# 611_jetbot_128.net
KiCad netlist of a schematic drawn in EAGLE
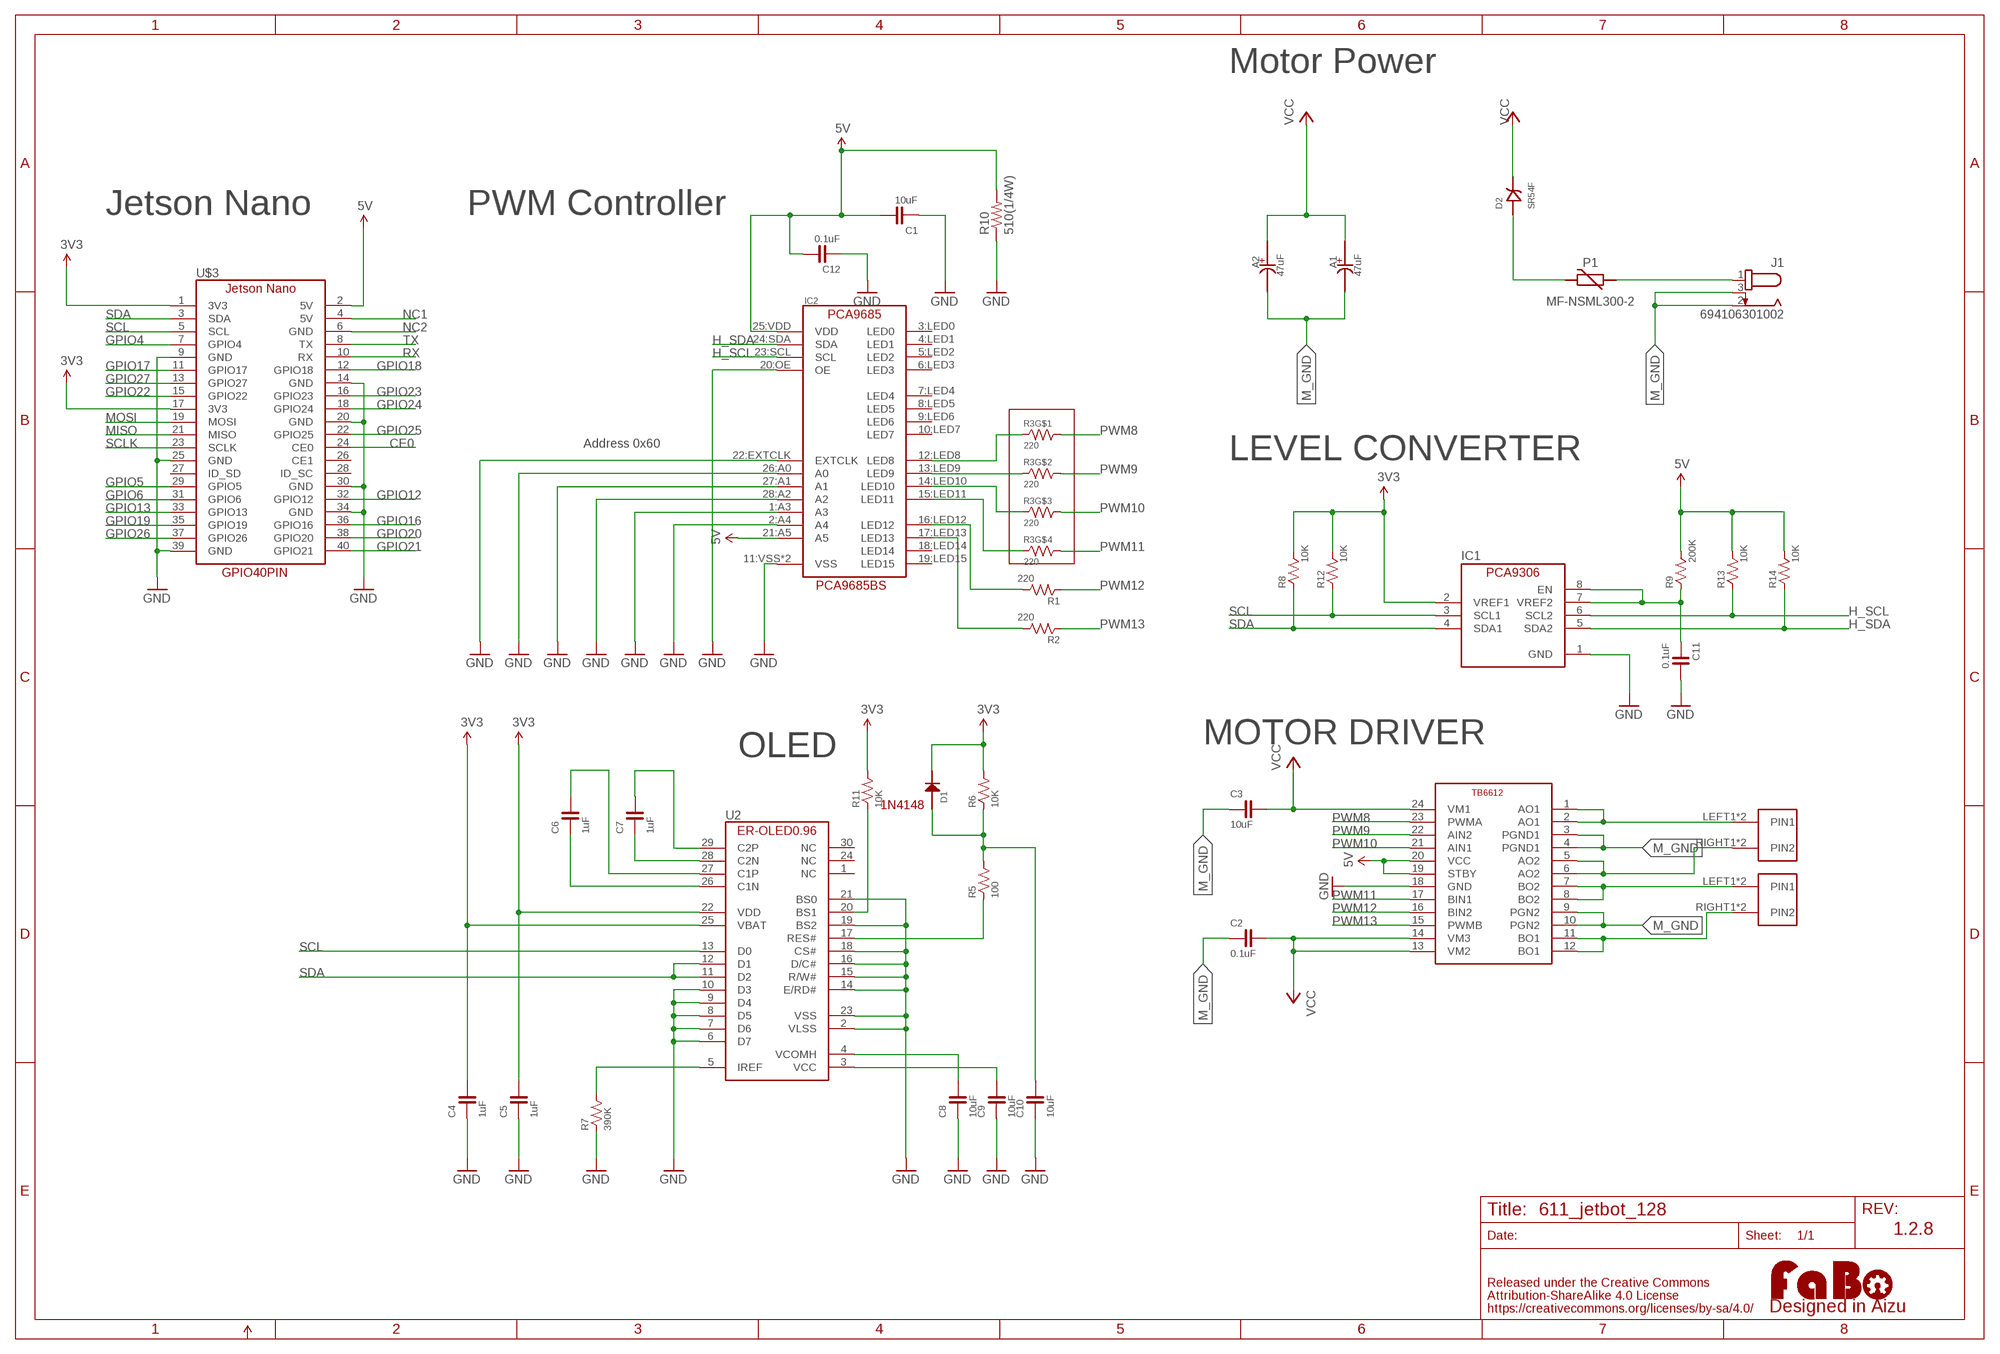
[diagram p0: schematic, sheet 1]

(export (version "E")
  (design (tool "Eeschema 10.0.6"))
  (components
    (comp (ref "A1")
      (value "47uF")
      (footprint "eagle-import:D60")
      (libsource (lib "eagle-import") (part "CAPACITOR-ALUMIN_D60"))
    )
    (comp (ref "A2")
      (value "47uF")
      (footprint "eagle-import:D60")
      (libsource (lib "eagle-import") (part "CAPACITOR-ALUMIN_D60"))
    )
    (comp (ref "C1")
      (value "10uF")
      (footprint "eagle-import:0603")
      (libsource (lib "eagle-import") (part "CAPACITOR-0603"))
    )
    (comp (ref "C2")
      (value "0.1uF")
      (footprint "eagle-import:0603")
      (libsource (lib "eagle-import") (part "CAPACITOR-0603"))
    )
    (comp (ref "C3")
      (value "10uF")
      (footprint "eagle-import:0603")
      (libsource (lib "eagle-import") (part "CAPACITOR-0603"))
    )
    (comp (ref "C4")
      (value "1uF")
      (footprint "eagle-import:0603-BOTTOM")
      (libsource (lib "eagle-import") (part "CAPACITOR-0603-BOTTOM"))
    )
    (comp (ref "C5")
      (value "1uF")
      (footprint "eagle-import:0603-BOTTOM")
      (libsource (lib "eagle-import") (part "CAPACITOR-0603-BOTTOM"))
    )
    (comp (ref "C6")
      (value "1uF")
      (footprint "eagle-import:0603-BOTTOM")
      (libsource (lib "eagle-import") (part "CAPACITOR-0603-BOTTOM"))
    )
    (comp (ref "C7")
      (value "1uF")
      (footprint "eagle-import:0603-BOTTOM")
      (libsource (lib "eagle-import") (part "CAPACITOR-0603-BOTTOM"))
    )
    (comp (ref "C8")
      (value "10uF")
      (footprint "eagle-import:0603-BOTTOM")
      (libsource (lib "eagle-import") (part "CAPACITOR-0603-BOTTOM"))
    )
    (comp (ref "C9")
      (value "10uF")
      (footprint "eagle-import:0603-BOTTOM")
      (libsource (lib "eagle-import") (part "CAPACITOR-0603-BOTTOM"))
    )
    (comp (ref "C10")
      (value "10uF")
      (footprint "eagle-import:0603-BOTTOM")
      (libsource (lib "eagle-import") (part "CAPACITOR-0603-BOTTOM"))
    )
    (comp (ref "C11")
      (value "0.1uF")
      (footprint "eagle-import:0603")
      (libsource (lib "eagle-import") (part "CAPACITOR-0603"))
    )
    (comp (ref "C12")
      (value "0.1uF")
      (footprint "eagle-import:0603")
      (libsource (lib "eagle-import") (part "CAPACITOR-0603"))
    )
    (comp (ref "D1")
      (value "1N4148")
      (footprint "eagle-import:1N4148W")
      (libsource (lib "eagle-import") (part "1N4148"))
    )
    (comp (ref "D2")
      (value "SR54F")
      (footprint "eagle-import:SMBF")
      (libsource (lib "eagle-import") (part "SR54F"))
    )
    (comp (ref "IC1")
      (value "PCA9306_SSOP")
      (footprint "eagle-import:8PIN-SSOP")
      (libsource (lib "eagle-import") (part "PCA9306_SSOP"))
    )
    (comp (ref "IC2")
      (value "PCA9685BSPCA9685BS")
      (footprint "eagle-import:HVQFN28")
      (libsource (lib "eagle-import") (part "PCA9685BSPCA9685BS"))
    )
    (comp (ref "J1")
      (value "694106301002")
      (footprint "eagle-import:694106301002")
      (fields
        (field (name "DIGIKEY_PART_NUMBER") "732-5930-ND")
        (field (name "MANUFACTURER") "Wurth Electronics Inc.")
        (field (name "CREATED_BY") "PCBLayout.com")
      )
      (libsource (lib "eagle-import") (part "694106301002"))
    )
    (comp (ref "LOGO1")
      (value "LOGO_FABO-M")
      (footprint "eagle-import:LOGO_FABO_M")
      (libsource (lib "eagle-import") (part "LOGO_FABO-M"))
    )
    (comp (ref "P1")
      (value "MF-NSML300-2")
      (footprint "eagle-import:1206")
      (libsource (lib "eagle-import") (part "POLYSWITCH1206"))
    )
    (comp (ref "R1")
      (value "220")
      (footprint "eagle-import:0603")
      (libsource (lib "eagle-import") (part "RESISTOR-0603"))
    )
    (comp (ref "R2")
      (value "220")
      (footprint "eagle-import:0603")
      (libsource (lib "eagle-import") (part "RESISTOR-0603"))
    )
    (comp (ref "R3")
      (value "220")
      (footprint "eagle-import:EXBV8V")
      (libsource (lib "eagle-import") (part "RESISTOR_ARRAY"))
    )
    (comp (ref "R5")
      (value "100")
      (footprint "eagle-import:0603-BOTTOM")
      (libsource (lib "eagle-import") (part "RESISTOR-0603-BOTTOM"))
    )
    (comp (ref "R6")
      (value "10K")
      (footprint "eagle-import:0603-BOTTOM")
      (libsource (lib "eagle-import") (part "RESISTOR-0603-BOTTOM"))
    )
    (comp (ref "R7")
      (value "390K")
      (footprint "eagle-import:0603-BOTTOM")
      (libsource (lib "eagle-import") (part "RESISTOR-0603-BOTTOM"))
    )
    (comp (ref "R8")
      (value "10K")
      (footprint "eagle-import:0603")
      (libsource (lib "eagle-import") (part "RESISTOR-0603"))
    )
    (comp (ref "R9")
      (value "200K")
      (footprint "eagle-import:0603")
      (libsource (lib "eagle-import") (part "RESISTOR-0603"))
    )
    (comp (ref "R10")
      (value "510(1/4W)")
      (footprint "eagle-import:R0805")
      (libsource (lib "eagle-import") (part "R-US_R0805"))
    )
    (comp (ref "R11")
      (value "10K")
      (footprint "eagle-import:0603-BOTTOM")
      (libsource (lib "eagle-import") (part "RESISTOR-0603-BOTTOM"))
    )
    (comp (ref "R12")
      (value "10K")
      (footprint "eagle-import:0603")
      (libsource (lib "eagle-import") (part "RESISTOR-0603"))
    )
    (comp (ref "R13")
      (value "10K")
      (footprint "eagle-import:0603")
      (libsource (lib "eagle-import") (part "RESISTOR-0603"))
    )
    (comp (ref "R14")
      (value "10K")
      (footprint "eagle-import:0603")
      (libsource (lib "eagle-import") (part "RESISTOR-0603"))
    )
    (comp (ref "U$3")
      (value "JETSON_NANO")
      (footprint "eagle-import:JETSON_NANO")
      (libsource (lib "eagle-import") (part "JETSON_NANO"))
    )
    (comp (ref "U$5")
      (value "TB6612")
      (footprint "eagle-import:TB6612")
      (libsource (lib "eagle-import") (part "TB6612"))
    )
    (comp (ref "U$6")
      (value "ML-1400-S1")
      (footprint "eagle-import:ML-1400-S1")
      (libsource (lib "eagle-import") (part "ML-1400-S1"))
    )
    (comp (ref "U$8")
      (value "ML-1400-S1")
      (footprint "eagle-import:ML-1400-S1")
      (libsource (lib "eagle-import") (part "ML-1400-S1"))
    )
    (comp (ref "U2")
      (value "ER-OLED0.96-1ER-CON30HT-1_REV2")
      (footprint "eagle-import:ER-CON30HT-1_REV2")
      (libsource (lib "eagle-import") (part "ER-OLED0.96-1ER-CON30HT-1_REV2"))
    )
  )
  (nets
    (net (code "1") (name "/CE0") (class "Default")
      (node (ref "U$3") (pin "24") (pinfunction "CE0_24") (pintype "bidirectional"))
    )
    (net (code "2") (name "/GPIO4") (class "Default")
      (node (ref "U$3") (pin "7") (pinfunction "GPIO4_7") (pintype "bidirectional"))
    )
    (net (code "3") (name "/GPIO5") (class "Default")
      (node (ref "U$3") (pin "29") (pinfunction "GPIO5_29") (pintype "bidirectional"))
    )
    (net (code "4") (name "/GPIO6") (class "Default")
      (node (ref "U$3") (pin "31") (pinfunction "GPIO6_31") (pintype "bidirectional"))
    )
    (net (code "5") (name "/GPIO12") (class "Default")
      (node (ref "U$3") (pin "32") (pinfunction "GPIO12_32") (pintype "bidirectional"))
    )
    (net (code "6") (name "/GPIO13") (class "Default")
      (node (ref "U$3") (pin "33") (pinfunction "GPIO13_33") (pintype "bidirectional"))
    )
    (net (code "7") (name "/GPIO16") (class "Default")
      (node (ref "U$3") (pin "36") (pinfunction "GPIO16_36") (pintype "bidirectional"))
    )
    (net (code "8") (name "/GPIO17") (class "Default")
      (node (ref "U$3") (pin "11") (pinfunction "GPIO17_11") (pintype "bidirectional"))
    )
    (net (code "9") (name "/GPIO18") (class "Default")
      (node (ref "U$3") (pin "12") (pinfunction "GPIO18_12") (pintype "bidirectional"))
    )
    (net (code "10") (name "/GPIO19") (class "Default")
      (node (ref "U$3") (pin "35") (pinfunction "GPIO19_35") (pintype "bidirectional"))
    )
    (net (code "11") (name "/GPIO20") (class "Default")
      (node (ref "U$3") (pin "38") (pinfunction "GPIO20_38") (pintype "bidirectional"))
    )
    (net (code "12") (name "/GPIO21") (class "Default")
      (node (ref "U$3") (pin "40") (pinfunction "GPIO21_40") (pintype "bidirectional"))
    )
    (net (code "13") (name "/GPIO22") (class "Default")
      (node (ref "U$3") (pin "15") (pinfunction "GPIO22_15") (pintype "bidirectional"))
    )
    (net (code "14") (name "/GPIO23") (class "Default")
      (node (ref "U$3") (pin "16") (pinfunction "GPIO23_16") (pintype "bidirectional"))
    )
    (net (code "15") (name "/GPIO24") (class "Default")
      (node (ref "U$3") (pin "18") (pinfunction "GPIO24_18") (pintype "bidirectional"))
    )
    (net (code "16") (name "/GPIO25") (class "Default")
      (node (ref "U$3") (pin "22") (pinfunction "GPIO25_22") (pintype "bidirectional"))
    )
    (net (code "17") (name "/GPIO26") (class "Default")
      (node (ref "U$3") (pin "37") (pinfunction "GPIO26_37") (pintype "bidirectional"))
    )
    (net (code "18") (name "/GPIO27") (class "Default")
      (node (ref "U$3") (pin "13") (pinfunction "GPIO27_13") (pintype "bidirectional"))
    )
    (net (code "19") (name "/H_SCL") (class "Default")
      (node (ref "IC1") (pin "6") (pinfunction "SCL2_6") (pintype "bidirectional"))
      (node (ref "IC2") (pin "23:SCL") (pinfunction "SCL_23:SCL") (pintype "bidirectional"))
      (node (ref "R13") (pin "1") (pinfunction "1_1") (pintype "bidirectional"))
    )
    (net (code "20") (name "/H_SDA") (class "Default")
      (node (ref "IC1") (pin "5") (pinfunction "SDA2_5") (pintype "bidirectional"))
      (node (ref "IC2") (pin "24:SDA") (pinfunction "SDA_24:SDA") (pintype "bidirectional"))
      (node (ref "R14") (pin "1") (pinfunction "1_1") (pintype "bidirectional"))
    )
    (net (code "21") (name "/MISO") (class "Default")
      (node (ref "U$3") (pin "21") (pinfunction "MISO_21") (pintype "bidirectional"))
    )
    (net (code "22") (name "/MOSI") (class "Default")
      (node (ref "U$3") (pin "19") (pinfunction "MOSI_19") (pintype "bidirectional"))
    )
    (net (code "23") (name "/NC1") (class "Default")
      (node (ref "U$3") (pin "4") (pinfunction "5V_4") (pintype "bidirectional"))
    )
    (net (code "24") (name "/NC2") (class "Default")
      (node (ref "U$3") (pin "6") (pinfunction "GND_6") (pintype "bidirectional"))
    )
    (net (code "25") (name "/PWM8") (class "Default")
      (node (ref "R3") (pin "8") (pinfunction "2_8") (pintype "bidirectional"))
      (node (ref "U$5") (pin "23") (pinfunction "PWMA_23") (pintype "bidirectional"))
    )
    (net (code "26") (name "/PWM9") (class "Default")
      (node (ref "R3") (pin "7") (pinfunction "2_7") (pintype "bidirectional"))
      (node (ref "U$5") (pin "22") (pinfunction "AIN2_22") (pintype "bidirectional"))
    )
    (net (code "27") (name "/PWM10") (class "Default")
      (node (ref "R3") (pin "6") (pinfunction "2_6") (pintype "bidirectional"))
      (node (ref "U$5") (pin "21") (pinfunction "AIN1_21") (pintype "bidirectional"))
    )
    (net (code "28") (name "/PWM11") (class "Default")
      (node (ref "R3") (pin "5") (pinfunction "2_5") (pintype "bidirectional"))
      (node (ref "U$5") (pin "17") (pinfunction "BIN1_17") (pintype "bidirectional"))
    )
    (net (code "29") (name "/PWM12") (class "Default")
      (node (ref "R1") (pin "1") (pinfunction "1_1") (pintype "bidirectional"))
      (node (ref "U$5") (pin "16") (pinfunction "BIN2_16") (pintype "bidirectional"))
    )
    (net (code "30") (name "/PWM13") (class "Default")
      (node (ref "R2") (pin "1") (pinfunction "1_1") (pintype "bidirectional"))
      (node (ref "U$5") (pin "15") (pinfunction "PWMB_15") (pintype "bidirectional"))
    )
    (net (code "31") (name "/RX") (class "Default")
      (node (ref "U$3") (pin "10") (pinfunction "RX_10") (pintype "bidirectional"))
    )
    (net (code "32") (name "/SCL") (class "Default")
      (node (ref "IC1") (pin "3") (pinfunction "SCL1_3") (pintype "bidirectional"))
      (node (ref "R12") (pin "1") (pinfunction "1_1") (pintype "bidirectional"))
      (node (ref "U$3") (pin "5") (pinfunction "SCL_5") (pintype "bidirectional"))
      (node (ref "U2") (pin "13") (pinfunction "D0_13") (pintype "bidirectional"))
    )
    (net (code "33") (name "/SCLK") (class "Default")
      (node (ref "U$3") (pin "23") (pinfunction "SCLK_23") (pintype "bidirectional"))
    )
    (net (code "34") (name "/SDA") (class "Default")
      (node (ref "IC1") (pin "4") (pinfunction "SDA1_4") (pintype "bidirectional"))
      (node (ref "R8") (pin "1") (pinfunction "1_1") (pintype "bidirectional"))
      (node (ref "U$3") (pin "3") (pinfunction "SDA_3") (pintype "bidirectional"))
      (node (ref "U2") (pin "11") (pinfunction "D2_11") (pintype "bidirectional"))
      (node (ref "U2") (pin "12") (pinfunction "D1_12") (pintype "bidirectional"))
    )
    (net (code "35") (name "/TX") (class "Default")
      (node (ref "U$3") (pin "8") (pinfunction "TX_8") (pintype "bidirectional"))
    )
    (net (code "36") (name "3V3") (class "Default")
      (node (ref "C4") (pin "2") (pinfunction "2_2") (pintype "passive"))
      (node (ref "C5") (pin "2") (pinfunction "2_2") (pintype "passive"))
      (node (ref "D1") (pin "CATHODE") (pinfunction "CATHODE_CATHODE") (pintype "bidirectional"))
      (node (ref "IC1") (pin "2") (pinfunction "VREF1_2") (pintype "bidirectional"))
      (node (ref "R11") (pin "2") (pinfunction "2_2") (pintype "bidirectional"))
      (node (ref "R12") (pin "2") (pinfunction "2_2") (pintype "bidirectional"))
      (node (ref "R6") (pin "2") (pinfunction "2_2") (pintype "bidirectional"))
      (node (ref "R8") (pin "2") (pinfunction "2_2") (pintype "bidirectional"))
      (node (ref "U$3") (pin "1") (pinfunction "3V3_1") (pintype "bidirectional"))
      (node (ref "U$3") (pin "17") (pinfunction "3V3_17") (pintype "bidirectional"))
      (node (ref "U2") (pin "22") (pinfunction "VDD_22") (pintype "bidirectional"))
      (node (ref "U2") (pin "25") (pinfunction "VBAT_25") (pintype "bidirectional"))
    )
    (net (code "37") (name "5V") (class "Default")
      (node (ref "C1") (pin "2") (pinfunction "2_2") (pintype "passive"))
      (node (ref "C12") (pin "2") (pinfunction "2_2") (pintype "passive"))
      (node (ref "IC2") (pin "21:A5") (pinfunction "A5_21:A5") (pintype "bidirectional"))
      (node (ref "IC2") (pin "25:VDD") (pinfunction "VDD_25:VDD") (pintype "bidirectional"))
      (node (ref "R10") (pin "2") (pinfunction "2_2") (pintype "passive"))
      (node (ref "R13") (pin "2") (pinfunction "2_2") (pintype "bidirectional"))
      (node (ref "R14") (pin "2") (pinfunction "2_2") (pintype "bidirectional"))
      (node (ref "R9") (pin "2") (pinfunction "2_2") (pintype "bidirectional"))
      (node (ref "U$3") (pin "2") (pinfunction "5V_2") (pintype "bidirectional"))
      (node (ref "U$5") (pin "19") (pinfunction "STBY_19") (pintype "bidirectional"))
      (node (ref "U$5") (pin "20") (pinfunction "VCC_20") (pintype "bidirectional"))
    )
    (net (code "38") (name "GND") (class "Default")
      (node (ref "C1") (pin "1") (pinfunction "1_1") (pintype "passive"))
      (node (ref "C10") (pin "1") (pinfunction "1_1") (pintype "passive"))
      (node (ref "C11") (pin "2") (pinfunction "2_2") (pintype "passive"))
      (node (ref "C12") (pin "1") (pinfunction "1_1") (pintype "passive"))
      (node (ref "C4") (pin "1") (pinfunction "1_1") (pintype "passive"))
      (node (ref "C5") (pin "1") (pinfunction "1_1") (pintype "passive"))
      (node (ref "C8") (pin "1") (pinfunction "1_1") (pintype "passive"))
      (node (ref "C9") (pin "1") (pinfunction "1_1") (pintype "passive"))
      (node (ref "IC1") (pin "1") (pinfunction "GND_1") (pintype "bidirectional"))
      (node (ref "IC2") (pin "11:VSS") (pinfunction "VSS_11:VSS") (pintype "bidirectional"))
      (node (ref "IC2") (pin "1:A3") (pinfunction "A3_1:A3") (pintype "bidirectional"))
      (node (ref "IC2") (pin "20:OE") (pinfunction "OE_20:OE") (pintype "bidirectional"))
      (node (ref "IC2") (pin "22:EXTCLK") (pinfunction "EXTCLK_22:EXTCLK") (pintype "bidirectional"))
      (node (ref "IC2") (pin "26:A0") (pinfunction "A0_26:A0") (pintype "bidirectional"))
      (node (ref "IC2") (pin "27:A1") (pinfunction "A1_27:A1") (pintype "bidirectional"))
      (node (ref "IC2") (pin "28:A2") (pinfunction "A2_28:A2") (pintype "bidirectional"))
      (node (ref "IC2") (pin "29") (pinfunction "VSS_29") (pintype "bidirectional"))
      (node (ref "IC2") (pin "2:A4") (pinfunction "A4_2:A4") (pintype "bidirectional"))
      (node (ref "R10") (pin "1") (pinfunction "1_1") (pintype "passive"))
      (node (ref "R7") (pin "1") (pinfunction "1_1") (pintype "bidirectional"))
      (node (ref "U$3") (pin "14") (pinfunction "GND_14") (pintype "bidirectional"))
      (node (ref "U$3") (pin "20") (pinfunction "GND_20") (pintype "bidirectional"))
      (node (ref "U$3") (pin "25") (pinfunction "GND_25") (pintype "bidirectional"))
      (node (ref "U$3") (pin "30") (pinfunction "GND_30") (pintype "bidirectional"))
      (node (ref "U$3") (pin "34") (pinfunction "GND_34") (pintype "bidirectional"))
      (node (ref "U$3") (pin "39") (pinfunction "GND_39") (pintype "bidirectional"))
      (node (ref "U$3") (pin "9") (pinfunction "GND_9") (pintype "bidirectional"))
      (node (ref "U$5") (pin "18") (pinfunction "GND_18") (pintype "bidirectional"))
      (node (ref "U2") (pin "10") (pinfunction "D3_10") (pintype "bidirectional"))
      (node (ref "U2") (pin "14") (pinfunction "E/RD#_14") (pintype "bidirectional"))
      (node (ref "U2") (pin "15") (pinfunction "R/W#_15") (pintype "bidirectional"))
      (node (ref "U2") (pin "16") (pinfunction "D/C#_16") (pintype "bidirectional"))
      (node (ref "U2") (pin "18") (pinfunction "CS#_18") (pintype "bidirectional"))
      (node (ref "U2") (pin "19") (pinfunction "BS2_19") (pintype "bidirectional"))
      (node (ref "U2") (pin "2") (pinfunction "VLSS_2") (pintype "bidirectional"))
      (node (ref "U2") (pin "21") (pinfunction "BS0_21") (pintype "bidirectional"))
      (node (ref "U2") (pin "23") (pinfunction "VSS_23") (pintype "bidirectional"))
      (node (ref "U2") (pin "6") (pinfunction "D7_6") (pintype "bidirectional"))
      (node (ref "U2") (pin "7") (pinfunction "D6_7") (pintype "bidirectional"))
      (node (ref "U2") (pin "8") (pinfunction "D5_8") (pintype "bidirectional"))
      (node (ref "U2") (pin "9") (pinfunction "D4_9") (pintype "bidirectional"))
    )
    (net (code "39") (name "M_GND") (class "Default")
      (node (ref "A1") (pin "MINUS") (pinfunction "-_MINUS") (pintype "passive"))
      (node (ref "A2") (pin "MINUS") (pinfunction "-_MINUS") (pintype "passive"))
      (node (ref "C2") (pin "1") (pinfunction "1_1") (pintype "passive"))
      (node (ref "C3") (pin "1") (pinfunction "1_1") (pintype "passive"))
      (node (ref "J1") (pin "2") (pinfunction "2_2") (pintype "passive"))
      (node (ref "J1") (pin "3") (pinfunction "3_3") (pintype "passive"))
      (node (ref "U$5") (pin "10") (pinfunction "PGN2_10") (pintype "bidirectional"))
      (node (ref "U$5") (pin "3") (pinfunction "PGND1_3") (pintype "bidirectional"))
      (node (ref "U$5") (pin "4") (pinfunction "PGND1_4") (pintype "bidirectional"))
      (node (ref "U$5") (pin "9") (pinfunction "PGN2_9") (pintype "bidirectional"))
    )
    (net (code "40") (name "Net-(C10-Pad2)") (class "Default")
      (node (ref "C10") (pin "2") (pinfunction "2_2") (pintype "passive"))
      (node (ref "D1") (pin "ANODE") (pinfunction "ANODE_ANODE") (pintype "bidirectional"))
      (node (ref "R5") (pin "2") (pinfunction "2_2") (pintype "bidirectional"))
      (node (ref "R6") (pin "1") (pinfunction "1_1") (pintype "bidirectional"))
    )
    (net (code "41") (name "Net-(D2-PadANODE)") (class "Default")
      (node (ref "D2") (pin "ANODE") (pinfunction "ANODE_ANODE") (pintype "bidirectional"))
      (node (ref "P1") (pin "2") (pinfunction "2_2") (pintype "bidirectional"))
    )
    (net (code "42") (name "Net-(IC1-EN)") (class "Default")
      (node (ref "C11") (pin "1") (pinfunction "1_1") (pintype "passive"))
      (node (ref "IC1") (pin "7") (pinfunction "VREF2_7") (pintype "bidirectional"))
      (node (ref "IC1") (pin "8") (pinfunction "EN_8") (pintype "bidirectional"))
      (node (ref "R9") (pin "1") (pinfunction "1_1") (pintype "bidirectional"))
    )
    (net (code "43") (name "Net-(IC2-LED8)") (class "Default")
      (node (ref "IC2") (pin "12:LED8") (pinfunction "LED8_12:LED8") (pintype "bidirectional"))
      (node (ref "R3") (pin "1") (pinfunction "1_1") (pintype "bidirectional"))
    )
    (net (code "44") (name "Net-(IC2-LED9)") (class "Default")
      (node (ref "IC2") (pin "13:LED9") (pinfunction "LED9_13:LED9") (pintype "bidirectional"))
      (node (ref "R3") (pin "2") (pinfunction "1_2") (pintype "bidirectional"))
    )
    (net (code "45") (name "Net-(IC2-LED10)") (class "Default")
      (node (ref "IC2") (pin "14:LED10") (pinfunction "LED10_14:LED10") (pintype "bidirectional"))
      (node (ref "R3") (pin "3") (pinfunction "1_3") (pintype "bidirectional"))
    )
    (net (code "46") (name "Net-(IC2-LED11)") (class "Default")
      (node (ref "IC2") (pin "15:LED11") (pinfunction "LED11_15:LED11") (pintype "bidirectional"))
      (node (ref "R3") (pin "4") (pinfunction "1_4") (pintype "bidirectional"))
    )
    (net (code "47") (name "Net-(IC2-LED12)") (class "Default")
      (node (ref "IC2") (pin "16:LED12") (pinfunction "LED12_16:LED12") (pintype "bidirectional"))
      (node (ref "R1") (pin "2") (pinfunction "2_2") (pintype "bidirectional"))
    )
    (net (code "48") (name "Net-(IC2-LED13)") (class "Default")
      (node (ref "IC2") (pin "17:LED13") (pinfunction "LED13_17:LED13") (pintype "bidirectional"))
      (node (ref "R2") (pin "2") (pinfunction "2_2") (pintype "bidirectional"))
    )
    (net (code "49") (name "Net-(J1-Pad1)") (class "Default")
      (node (ref "J1") (pin "1") (pinfunction "1_1") (pintype "passive"))
      (node (ref "P1") (pin "1") (pinfunction "1_1") (pintype "bidirectional"))
    )
    (net (code "50") (name "Net-(U$5-AO1-Pad1)") (class "Default")
      (node (ref "U$5") (pin "1") (pinfunction "AO1_1") (pintype "bidirectional"))
      (node (ref "U$5") (pin "2") (pinfunction "AO1_2") (pintype "bidirectional"))
      (node (ref "U$6") (pin "LEFT1") (pinfunction "PIN1_LEFT1") (pintype "bidirectional"))
      (node (ref "U$6") (pin "LEFT2") (pinfunction "PIN1_LEFT2") (pintype "bidirectional"))
    )
    (net (code "51") (name "Net-(U$5-AO2-Pad5)") (class "Default")
      (node (ref "U$5") (pin "5") (pinfunction "AO2_5") (pintype "bidirectional"))
      (node (ref "U$5") (pin "6") (pinfunction "AO2_6") (pintype "bidirectional"))
      (node (ref "U$6") (pin "RIGHT1") (pinfunction "PIN2_RIGHT1") (pintype "bidirectional"))
      (node (ref "U$6") (pin "RIGHT2") (pinfunction "PIN2_RIGHT2") (pintype "bidirectional"))
    )
    (net (code "52") (name "Net-(U$5-BO1-Pad11)") (class "Default")
      (node (ref "U$5") (pin "11") (pinfunction "BO1_11") (pintype "bidirectional"))
      (node (ref "U$5") (pin "12") (pinfunction "BO1_12") (pintype "bidirectional"))
      (node (ref "U$8") (pin "RIGHT1") (pinfunction "PIN2_RIGHT1") (pintype "bidirectional"))
      (node (ref "U$8") (pin "RIGHT2") (pinfunction "PIN2_RIGHT2") (pintype "bidirectional"))
    )
    (net (code "53") (name "Net-(U$5-BO2-Pad7)") (class "Default")
      (node (ref "U$5") (pin "7") (pinfunction "BO2_7") (pintype "bidirectional"))
      (node (ref "U$5") (pin "8") (pinfunction "BO2_8") (pintype "bidirectional"))
      (node (ref "U$8") (pin "LEFT1") (pinfunction "PIN1_LEFT1") (pintype "bidirectional"))
      (node (ref "U$8") (pin "LEFT2") (pinfunction "PIN1_LEFT2") (pintype "bidirectional"))
    )
    (net (code "54") (name "Net-(U2-BS1)") (class "Default")
      (node (ref "R11") (pin "1") (pinfunction "1_1") (pintype "bidirectional"))
      (node (ref "U2") (pin "20") (pinfunction "BS1_20") (pintype "bidirectional"))
    )
    (net (code "55") (name "Net-(U2-C1N)") (class "Default")
      (node (ref "C6") (pin "1") (pinfunction "1_1") (pintype "passive"))
      (node (ref "U2") (pin "26") (pinfunction "C1N_26") (pintype "bidirectional"))
    )
    (net (code "56") (name "Net-(U2-C1P)") (class "Default")
      (node (ref "C6") (pin "2") (pinfunction "2_2") (pintype "passive"))
      (node (ref "U2") (pin "27") (pinfunction "C1P_27") (pintype "bidirectional"))
    )
    (net (code "57") (name "Net-(U2-C2N)") (class "Default")
      (node (ref "C7") (pin "1") (pinfunction "1_1") (pintype "passive"))
      (node (ref "U2") (pin "28") (pinfunction "C2N_28") (pintype "bidirectional"))
    )
    (net (code "58") (name "Net-(U2-C2P)") (class "Default")
      (node (ref "C7") (pin "2") (pinfunction "2_2") (pintype "passive"))
      (node (ref "U2") (pin "29") (pinfunction "C2P_29") (pintype "bidirectional"))
    )
    (net (code "59") (name "Net-(U2-IREF)") (class "Default")
      (node (ref "R7") (pin "2") (pinfunction "2_2") (pintype "bidirectional"))
      (node (ref "U2") (pin "5") (pinfunction "IREF_5") (pintype "bidirectional"))
    )
    (net (code "60") (name "Net-(U2-RES#)") (class "Default")
      (node (ref "R5") (pin "1") (pinfunction "1_1") (pintype "bidirectional"))
      (node (ref "U2") (pin "17") (pinfunction "RES#_17") (pintype "bidirectional"))
    )
    (net (code "61") (name "Net-(U2-VCC)") (class "Default")
      (node (ref "C9") (pin "2") (pinfunction "2_2") (pintype "passive"))
      (node (ref "U2") (pin "3") (pinfunction "VCC_3") (pintype "bidirectional"))
    )
    (net (code "62") (name "Net-(U2-VCOMH)") (class "Default")
      (node (ref "C8") (pin "2") (pinfunction "2_2") (pintype "passive"))
      (node (ref "U2") (pin "4") (pinfunction "VCOMH_4") (pintype "bidirectional"))
    )
    (net (code "63") (name "VCC") (class "Default")
      (node (ref "A1") (pin "PLUS") (pinfunction "+_PLUS") (pintype "passive"))
      (node (ref "A2") (pin "PLUS") (pinfunction "+_PLUS") (pintype "passive"))
      (node (ref "C2") (pin "2") (pinfunction "2_2") (pintype "passive"))
      (node (ref "C3") (pin "2") (pinfunction "2_2") (pintype "passive"))
      (node (ref "D2") (pin "CATHODE") (pinfunction "CATHODE_CATHODE") (pintype "bidirectional"))
      (node (ref "U$5") (pin "13") (pinfunction "VM2_13") (pintype "bidirectional"))
      (node (ref "U$5") (pin "14") (pinfunction "VM3_14") (pintype "bidirectional"))
      (node (ref "U$5") (pin "24") (pinfunction "VM1_24") (pintype "bidirectional"))
    )
    (net (code "64") (name "unconnected-(IC2-LED0-Pad3:LED0)") (class "Default")
      (node (ref "IC2") (pin "3:LED0") (pinfunction "LED0_3:LED0") (pintype "bidirectional"))
    )
    (net (code "65") (name "unconnected-(IC2-LED1-Pad4:LED1)") (class "Default")
      (node (ref "IC2") (pin "4:LED1") (pinfunction "LED1_4:LED1") (pintype "bidirectional"))
    )
    (net (code "66") (name "unconnected-(IC2-LED2-Pad5:LED2)") (class "Default")
      (node (ref "IC2") (pin "5:LED2") (pinfunction "LED2_5:LED2") (pintype "bidirectional"))
    )
    (net (code "67") (name "unconnected-(IC2-LED3-Pad6:LED3)") (class "Default")
      (node (ref "IC2") (pin "6:LED3") (pinfunction "LED3_6:LED3") (pintype "bidirectional"))
    )
    (net (code "68") (name "unconnected-(IC2-LED4-Pad7:LED4)") (class "Default")
      (node (ref "IC2") (pin "7:LED4") (pinfunction "LED4_7:LED4") (pintype "bidirectional"))
    )
    (net (code "69") (name "unconnected-(IC2-LED5-Pad8:LED5)") (class "Default")
      (node (ref "IC2") (pin "8:LED5") (pinfunction "LED5_8:LED5") (pintype "bidirectional"))
    )
    (net (code "70") (name "unconnected-(IC2-LED6-Pad9:LED6)") (class "Default")
      (node (ref "IC2") (pin "9:LED6") (pinfunction "LED6_9:LED6") (pintype "bidirectional"))
    )
    (net (code "71") (name "unconnected-(IC2-LED7-Pad10:LED7)") (class "Default")
      (node (ref "IC2") (pin "10:LED7") (pinfunction "LED7_10:LED7") (pintype "bidirectional"))
    )
    (net (code "72") (name "unconnected-(IC2-LED14-Pad18:LED14)") (class "Default")
      (node (ref "IC2") (pin "18:LED14") (pinfunction "LED14_18:LED14") (pintype "bidirectional"))
    )
    (net (code "73") (name "unconnected-(IC2-LED15-Pad19:LED15)") (class "Default")
      (node (ref "IC2") (pin "19:LED15") (pinfunction "LED15_19:LED15") (pintype "bidirectional"))
    )
    (net (code "74") (name "unconnected-(U$3-CE1-Pad26)") (class "Default")
      (node (ref "U$3") (pin "26") (pinfunction "CE1_26") (pintype "bidirectional"))
    )
    (net (code "75") (name "unconnected-(U$3-ID_SC-Pad28)") (class "Default")
      (node (ref "U$3") (pin "28") (pinfunction "ID_SC_28") (pintype "bidirectional"))
    )
    (net (code "76") (name "unconnected-(U$3-ID_SD-Pad27)") (class "Default")
      (node (ref "U$3") (pin "27") (pinfunction "ID_SD_27") (pintype "bidirectional"))
    )
    (net (code "77") (name "unconnected-(U2-NC-Pad1)") (class "Default")
      (node (ref "U2") (pin "1") (pinfunction "NC_1") (pintype "bidirectional"))
    )
    (net (code "78") (name "unconnected-(U2-NC-Pad24)") (class "Default")
      (node (ref "U2") (pin "24") (pinfunction "NC_24") (pintype "bidirectional"))
    )
    (net (code "79") (name "unconnected-(U2-NC-Pad30)") (class "Default")
      (node (ref "U2") (pin "30") (pinfunction "NC_30") (pintype "bidirectional"))
    )
  )
)
